# McPiFace-7Segment-V1.net
KiCad netlist of a schematic drawn in EAGLE
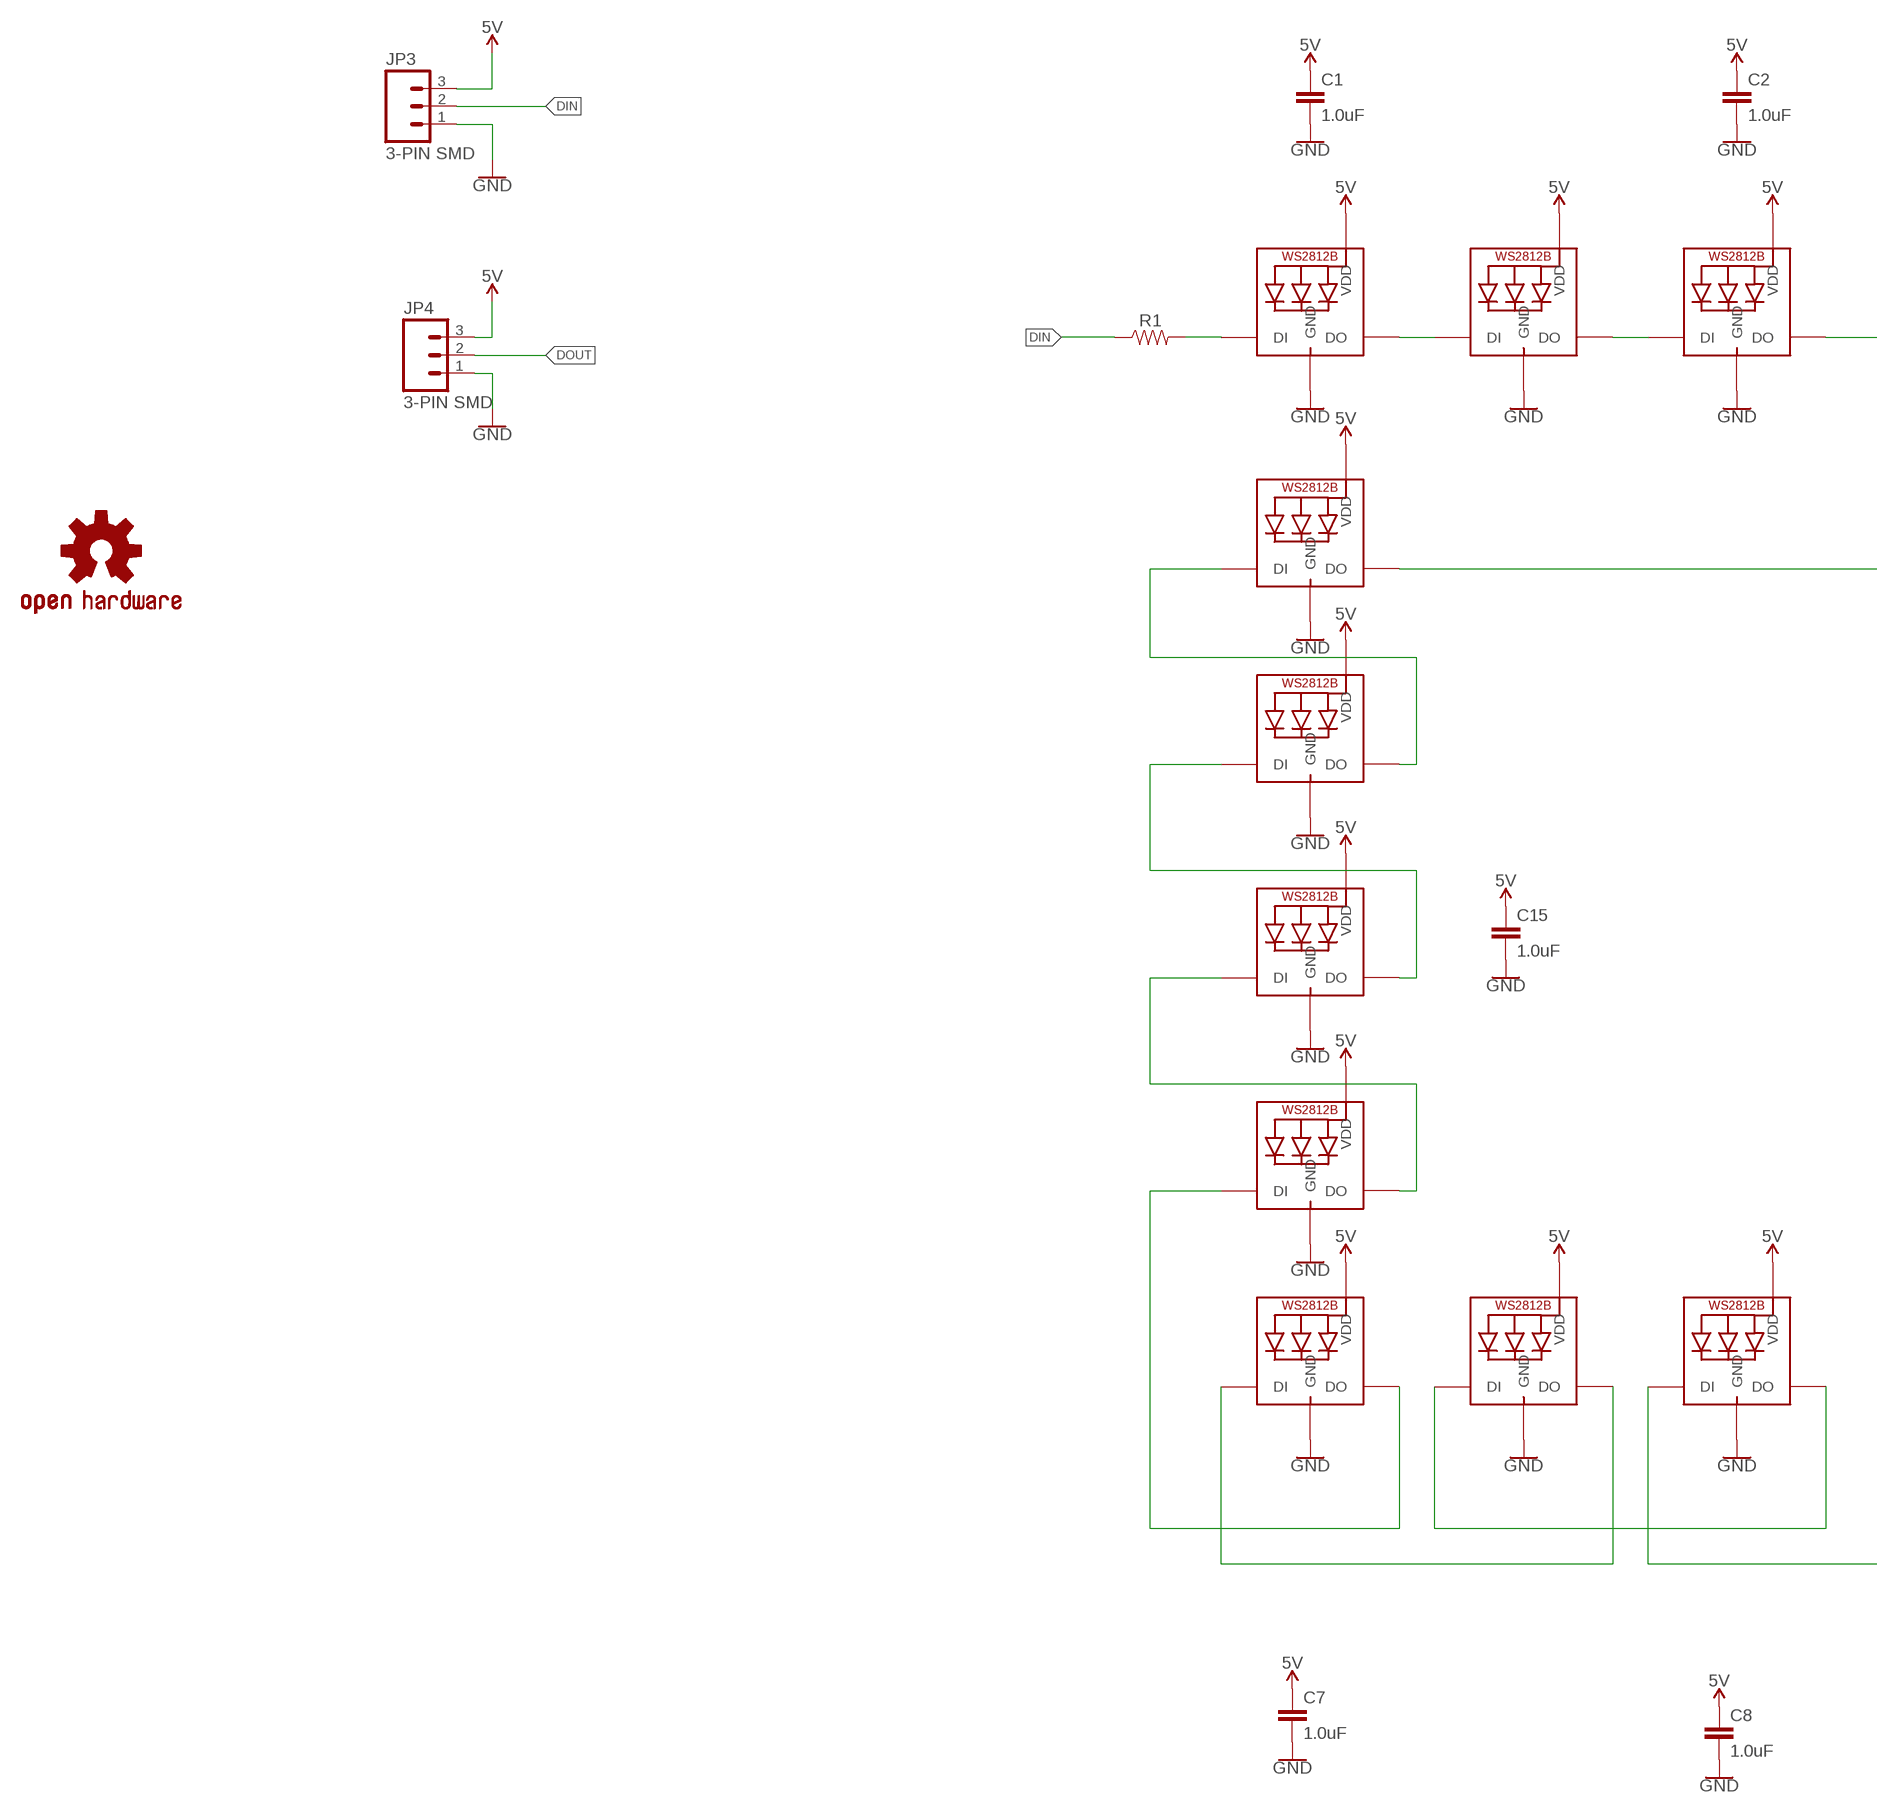
[diagram p0: schematic, sheet 1, part 1 of 2]
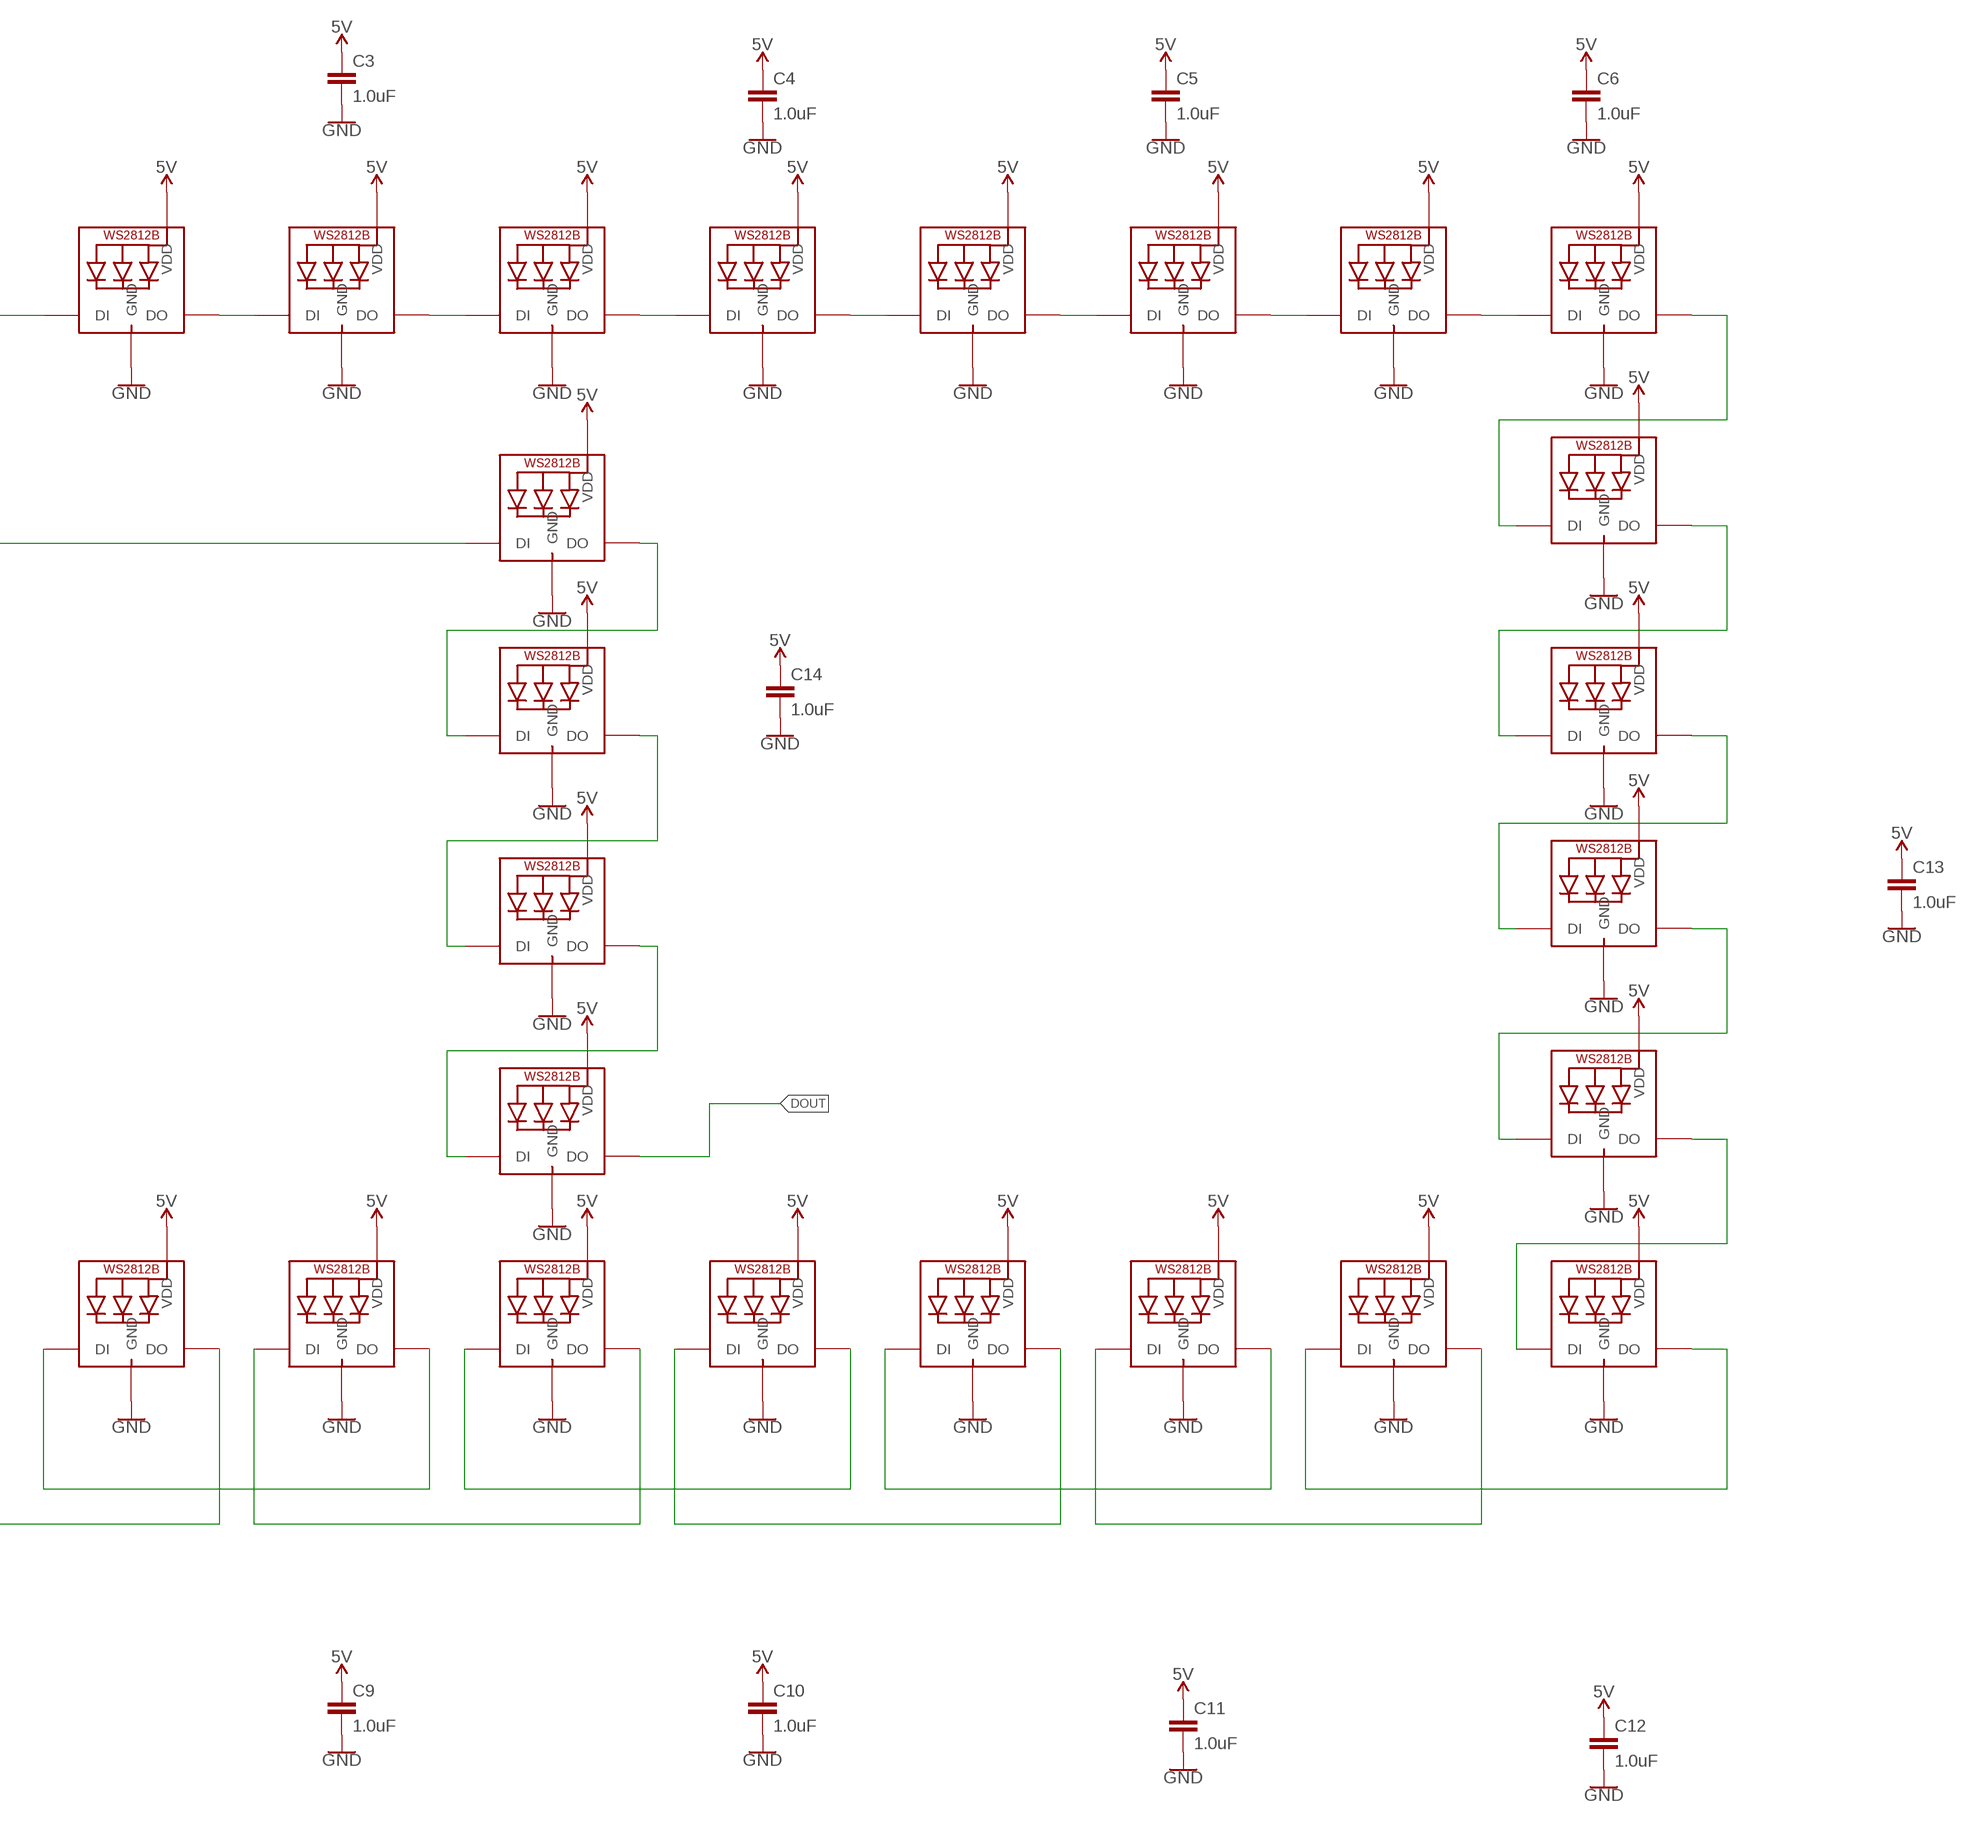
[diagram p1: schematic, sheet 1, part 2 of 2]

(export (version "E")
  (design (tool "Eeschema 10.0.6"))
  (components
    (comp (ref "C1")
      (value "1.0uF")
      (footprint "eagle-import:0805-CAP")
      (libsource (lib "eagle-import") (part "1.0UF-25V-+80/-20(0805){dblquote}"))
    )
    (comp (ref "C2")
      (value "1.0uF")
      (footprint "eagle-import:0805-CAP")
      (libsource (lib "eagle-import") (part "1.0UF-25V-+80/-20(0805){dblquote}"))
    )
    (comp (ref "C3")
      (value "1.0uF")
      (footprint "eagle-import:0805-CAP")
      (libsource (lib "eagle-import") (part "1.0UF-25V-+80/-20(0805){dblquote}"))
    )
    (comp (ref "C4")
      (value "1.0uF")
      (footprint "eagle-import:0805-CAP")
      (libsource (lib "eagle-import") (part "1.0UF-25V-+80/-20(0805){dblquote}"))
    )
    (comp (ref "C5")
      (value "1.0uF")
      (footprint "eagle-import:0805-CAP")
      (libsource (lib "eagle-import") (part "1.0UF-25V-+80/-20(0805){dblquote}"))
    )
    (comp (ref "C6")
      (value "1.0uF")
      (footprint "eagle-import:0805-CAP")
      (libsource (lib "eagle-import") (part "1.0UF-25V-+80/-20(0805){dblquote}"))
    )
    (comp (ref "C7")
      (value "1.0uF")
      (footprint "eagle-import:0805-CAP")
      (libsource (lib "eagle-import") (part "1.0UF-25V-+80/-20(0805){dblquote}"))
    )
    (comp (ref "C8")
      (value "1.0uF")
      (footprint "eagle-import:0805-CAP")
      (libsource (lib "eagle-import") (part "1.0UF-25V-+80/-20(0805){dblquote}"))
    )
    (comp (ref "C9")
      (value "1.0uF")
      (footprint "eagle-import:0805-CAP")
      (libsource (lib "eagle-import") (part "1.0UF-25V-+80/-20(0805){dblquote}"))
    )
    (comp (ref "C10")
      (value "1.0uF")
      (footprint "eagle-import:0805-CAP")
      (libsource (lib "eagle-import") (part "1.0UF-25V-+80/-20(0805){dblquote}"))
    )
    (comp (ref "C11")
      (value "1.0uF")
      (footprint "eagle-import:0805-CAP")
      (libsource (lib "eagle-import") (part "1.0UF-25V-+80/-20(0805){dblquote}"))
    )
    (comp (ref "C12")
      (value "1.0uF")
      (footprint "eagle-import:0805-CAP")
      (libsource (lib "eagle-import") (part "1.0UF-25V-+80/-20(0805){dblquote}"))
    )
    (comp (ref "C13")
      (value "1.0uF")
      (footprint "eagle-import:0805-CAP")
      (libsource (lib "eagle-import") (part "1.0UF-25V-+80/-20(0805){dblquote}"))
    )
    (comp (ref "C14")
      (value "1.0uF")
      (footprint "eagle-import:0805-CAP")
      (libsource (lib "eagle-import") (part "1.0UF-25V-+80/-20(0805){dblquote}"))
    )
    (comp (ref "C15")
      (value "1.0uF")
      (footprint "eagle-import:0805-CAP")
      (libsource (lib "eagle-import") (part "1.0UF-25V-+80/-20(0805){dblquote}"))
    )
    (comp (ref "JP3")
      (value "3-PIN SMD")
      (footprint "eagle-import:JST-3-SMD")
      (libsource (lib "eagle-import") (part "M03JST-SMD"))
    )
    (comp (ref "JP4")
      (value "3-PIN SMD")
      (footprint "eagle-import:JST-3-SMD")
      (libsource (lib "eagle-import") (part "M03JST-SMD"))
    )
    (comp (ref "LED1")
      (value "WS2812B5050")
      (footprint "eagle-import:WS2812B")
      (libsource (lib "eagle-import") (part "WS2812B5050"))
    )
    (comp (ref "LED2")
      (value "WS2812B5050")
      (footprint "eagle-import:WS2812B")
      (libsource (lib "eagle-import") (part "WS2812B5050"))
    )
    (comp (ref "LED3")
      (value "WS2812B5050")
      (footprint "eagle-import:WS2812B")
      (libsource (lib "eagle-import") (part "WS2812B5050"))
    )
    (comp (ref "LED4")
      (value "WS2812B5050")
      (footprint "eagle-import:WS2812B")
      (libsource (lib "eagle-import") (part "WS2812B5050"))
    )
    (comp (ref "LED5")
      (value "WS2812B5050")
      (footprint "eagle-import:WS2812B")
      (libsource (lib "eagle-import") (part "WS2812B5050"))
    )
    (comp (ref "LED6")
      (value "WS2812B5050")
      (footprint "eagle-import:WS2812B")
      (libsource (lib "eagle-import") (part "WS2812B5050"))
    )
    (comp (ref "LED7")
      (value "WS2812B5050")
      (footprint "eagle-import:WS2812B")
      (libsource (lib "eagle-import") (part "WS2812B5050"))
    )
    (comp (ref "LED8")
      (value "WS2812B5050")
      (footprint "eagle-import:WS2812B")
      (libsource (lib "eagle-import") (part "WS2812B5050"))
    )
    (comp (ref "LED9")
      (value "WS2812B5050")
      (footprint "eagle-import:WS2812B")
      (libsource (lib "eagle-import") (part "WS2812B5050"))
    )
    (comp (ref "LED10")
      (value "WS2812B5050")
      (footprint "eagle-import:WS2812B")
      (libsource (lib "eagle-import") (part "WS2812B5050"))
    )
    (comp (ref "LED11")
      (value "WS2812B5050")
      (footprint "eagle-import:WS2812B")
      (libsource (lib "eagle-import") (part "WS2812B5050"))
    )
    (comp (ref "LED12")
      (value "WS2812B5050")
      (footprint "eagle-import:WS2812B")
      (libsource (lib "eagle-import") (part "WS2812B5050"))
    )
    (comp (ref "LED13")
      (value "WS2812B5050")
      (footprint "eagle-import:WS2812B")
      (libsource (lib "eagle-import") (part "WS2812B5050"))
    )
    (comp (ref "LED14")
      (value "WS2812B5050")
      (footprint "eagle-import:WS2812B")
      (libsource (lib "eagle-import") (part "WS2812B5050"))
    )
    (comp (ref "LED15")
      (value "WS2812B5050")
      (footprint "eagle-import:WS2812B")
      (libsource (lib "eagle-import") (part "WS2812B5050"))
    )
    (comp (ref "LED16")
      (value "WS2812B5050")
      (footprint "eagle-import:WS2812B")
      (libsource (lib "eagle-import") (part "WS2812B5050"))
    )
    (comp (ref "LED17")
      (value "WS2812B5050")
      (footprint "eagle-import:WS2812B")
      (libsource (lib "eagle-import") (part "WS2812B5050"))
    )
    (comp (ref "LED18")
      (value "WS2812B5050")
      (footprint "eagle-import:WS2812B")
      (libsource (lib "eagle-import") (part "WS2812B5050"))
    )
    (comp (ref "LED19")
      (value "WS2812B5050")
      (footprint "eagle-import:WS2812B")
      (libsource (lib "eagle-import") (part "WS2812B5050"))
    )
    (comp (ref "LED20")
      (value "WS2812B5050")
      (footprint "eagle-import:WS2812B")
      (libsource (lib "eagle-import") (part "WS2812B5050"))
    )
    (comp (ref "LED21")
      (value "WS2812B5050")
      (footprint "eagle-import:WS2812B")
      (libsource (lib "eagle-import") (part "WS2812B5050"))
    )
    (comp (ref "LED22")
      (value "WS2812B5050")
      (footprint "eagle-import:WS2812B")
      (libsource (lib "eagle-import") (part "WS2812B5050"))
    )
    (comp (ref "LED23")
      (value "WS2812B5050")
      (footprint "eagle-import:WS2812B")
      (libsource (lib "eagle-import") (part "WS2812B5050"))
    )
    (comp (ref "LED24")
      (value "WS2812B5050")
      (footprint "eagle-import:WS2812B")
      (libsource (lib "eagle-import") (part "WS2812B5050"))
    )
    (comp (ref "LED25")
      (value "WS2812B5050")
      (footprint "eagle-import:WS2812B")
      (libsource (lib "eagle-import") (part "WS2812B5050"))
    )
    (comp (ref "LED26")
      (value "WS2812B5050")
      (footprint "eagle-import:WS2812B")
      (libsource (lib "eagle-import") (part "WS2812B5050"))
    )
    (comp (ref "LED27")
      (value "WS2812B5050")
      (footprint "eagle-import:WS2812B")
      (libsource (lib "eagle-import") (part "WS2812B5050"))
    )
    (comp (ref "LED28")
      (value "WS2812B5050")
      (footprint "eagle-import:WS2812B")
      (libsource (lib "eagle-import") (part "WS2812B5050"))
    )
    (comp (ref "LED29")
      (value "WS2812B5050")
      (footprint "eagle-import:WS2812B")
      (libsource (lib "eagle-import") (part "WS2812B5050"))
    )
    (comp (ref "LED30")
      (value "WS2812B5050")
      (footprint "eagle-import:WS2812B")
      (libsource (lib "eagle-import") (part "WS2812B5050"))
    )
    (comp (ref "LED31")
      (value "WS2812B5050")
      (footprint "eagle-import:WS2812B")
      (libsource (lib "eagle-import") (part "WS2812B5050"))
    )
    (comp (ref "LED32")
      (value "WS2812B5050")
      (footprint "eagle-import:WS2812B")
      (libsource (lib "eagle-import") (part "WS2812B5050"))
    )
    (comp (ref "LED33")
      (value "WS2812B5050")
      (footprint "eagle-import:WS2812B")
      (libsource (lib "eagle-import") (part "WS2812B5050"))
    )
    (comp (ref "LED34")
      (value "WS2812B5050")
      (footprint "eagle-import:WS2812B")
      (libsource (lib "eagle-import") (part "WS2812B5050"))
    )
    (comp (ref "LOGO1")
      (value "OSHW-LOGOL")
      (footprint "eagle-import:OSHW-LOGO-L")
      (libsource (lib "eagle-import") (part "OSHW-LOGOL"))
    )
    (comp (ref "R1")
      (value "RESISTOR0805")
      (footprint "eagle-import:0805")
      (libsource (lib "eagle-import") (part "RESISTOR0805"))
    )
  )
  (nets
    (net (code "1") (name "5V") (class "Default")
      (node (ref "C1") (pin "1") (pinfunction "1_1") (pintype "passive"))
      (node (ref "C10") (pin "1") (pinfunction "1_1") (pintype "passive"))
      (node (ref "C11") (pin "1") (pinfunction "1_1") (pintype "passive"))
      (node (ref "C12") (pin "1") (pinfunction "1_1") (pintype "passive"))
      (node (ref "C13") (pin "1") (pinfunction "1_1") (pintype "passive"))
      (node (ref "C14") (pin "1") (pinfunction "1_1") (pintype "passive"))
      (node (ref "C15") (pin "1") (pinfunction "1_1") (pintype "passive"))
      (node (ref "C2") (pin "1") (pinfunction "1_1") (pintype "passive"))
      (node (ref "C3") (pin "1") (pinfunction "1_1") (pintype "passive"))
      (node (ref "C4") (pin "1") (pinfunction "1_1") (pintype "passive"))
      (node (ref "C5") (pin "1") (pinfunction "1_1") (pintype "passive"))
      (node (ref "C6") (pin "1") (pinfunction "1_1") (pintype "passive"))
      (node (ref "C7") (pin "1") (pinfunction "1_1") (pintype "passive"))
      (node (ref "C8") (pin "1") (pinfunction "1_1") (pintype "passive"))
      (node (ref "C9") (pin "1") (pinfunction "1_1") (pintype "passive"))
      (node (ref "JP3") (pin "3") (pinfunction "3_3") (pintype "passive"))
      (node (ref "JP4") (pin "3") (pinfunction "3_3") (pintype "passive"))
      (node (ref "LED1") (pin "1-VDD") (pinfunction "VDD_1-VDD") (pintype "power_in"))
      (node (ref "LED10") (pin "1-VDD") (pinfunction "VDD_1-VDD") (pintype "power_in"))
      (node (ref "LED11") (pin "1-VDD") (pinfunction "VDD_1-VDD") (pintype "power_in"))
      (node (ref "LED12") (pin "1-VDD") (pinfunction "VDD_1-VDD") (pintype "power_in"))
      (node (ref "LED13") (pin "1-VDD") (pinfunction "VDD_1-VDD") (pintype "power_in"))
      (node (ref "LED14") (pin "1-VDD") (pinfunction "VDD_1-VDD") (pintype "power_in"))
      (node (ref "LED15") (pin "1-VDD") (pinfunction "VDD_1-VDD") (pintype "power_in"))
      (node (ref "LED16") (pin "1-VDD") (pinfunction "VDD_1-VDD") (pintype "power_in"))
      (node (ref "LED17") (pin "1-VDD") (pinfunction "VDD_1-VDD") (pintype "power_in"))
      (node (ref "LED18") (pin "1-VDD") (pinfunction "VDD_1-VDD") (pintype "power_in"))
      (node (ref "LED19") (pin "1-VDD") (pinfunction "VDD_1-VDD") (pintype "power_in"))
      (node (ref "LED2") (pin "1-VDD") (pinfunction "VDD_1-VDD") (pintype "power_in"))
      (node (ref "LED20") (pin "1-VDD") (pinfunction "VDD_1-VDD") (pintype "power_in"))
      (node (ref "LED21") (pin "1-VDD") (pinfunction "VDD_1-VDD") (pintype "power_in"))
      (node (ref "LED22") (pin "1-VDD") (pinfunction "VDD_1-VDD") (pintype "power_in"))
      (node (ref "LED23") (pin "1-VDD") (pinfunction "VDD_1-VDD") (pintype "power_in"))
      (node (ref "LED24") (pin "1-VDD") (pinfunction "VDD_1-VDD") (pintype "power_in"))
      (node (ref "LED25") (pin "1-VDD") (pinfunction "VDD_1-VDD") (pintype "power_in"))
      (node (ref "LED26") (pin "1-VDD") (pinfunction "VDD_1-VDD") (pintype "power_in"))
      (node (ref "LED27") (pin "1-VDD") (pinfunction "VDD_1-VDD") (pintype "power_in"))
      (node (ref "LED28") (pin "1-VDD") (pinfunction "VDD_1-VDD") (pintype "power_in"))
      (node (ref "LED29") (pin "1-VDD") (pinfunction "VDD_1-VDD") (pintype "power_in"))
      (node (ref "LED3") (pin "1-VDD") (pinfunction "VDD_1-VDD") (pintype "power_in"))
      (node (ref "LED30") (pin "1-VDD") (pinfunction "VDD_1-VDD") (pintype "power_in"))
      (node (ref "LED31") (pin "1-VDD") (pinfunction "VDD_1-VDD") (pintype "power_in"))
      (node (ref "LED32") (pin "1-VDD") (pinfunction "VDD_1-VDD") (pintype "power_in"))
      (node (ref "LED33") (pin "1-VDD") (pinfunction "VDD_1-VDD") (pintype "power_in"))
      (node (ref "LED34") (pin "1-VDD") (pinfunction "VDD_1-VDD") (pintype "power_in"))
      (node (ref "LED4") (pin "1-VDD") (pinfunction "VDD_1-VDD") (pintype "power_in"))
      (node (ref "LED5") (pin "1-VDD") (pinfunction "VDD_1-VDD") (pintype "power_in"))
      (node (ref "LED6") (pin "1-VDD") (pinfunction "VDD_1-VDD") (pintype "power_in"))
      (node (ref "LED7") (pin "1-VDD") (pinfunction "VDD_1-VDD") (pintype "power_in"))
      (node (ref "LED8") (pin "1-VDD") (pinfunction "VDD_1-VDD") (pintype "power_in"))
      (node (ref "LED9") (pin "1-VDD") (pinfunction "VDD_1-VDD") (pintype "power_in"))
    )
    (net (code "2") (name "DIN") (class "Default")
      (node (ref "JP3") (pin "2") (pinfunction "2_2") (pintype "passive"))
      (node (ref "R1") (pin "1") (pinfunction "1_1") (pintype "passive"))
    )
    (net (code "3") (name "DOUT") (class "Default")
      (node (ref "JP4") (pin "2") (pinfunction "2_2") (pintype "passive"))
      (node (ref "LED15") (pin "2-DOUT") (pinfunction "DO_2-DOUT") (pintype "output"))
    )
    (net (code "4") (name "GND") (class "Default")
      (node (ref "C1") (pin "2") (pinfunction "2_2") (pintype "passive"))
      (node (ref "C10") (pin "2") (pinfunction "2_2") (pintype "passive"))
      (node (ref "C11") (pin "2") (pinfunction "2_2") (pintype "passive"))
      (node (ref "C12") (pin "2") (pinfunction "2_2") (pintype "passive"))
      (node (ref "C13") (pin "2") (pinfunction "2_2") (pintype "passive"))
      (node (ref "C14") (pin "2") (pinfunction "2_2") (pintype "passive"))
      (node (ref "C15") (pin "2") (pinfunction "2_2") (pintype "passive"))
      (node (ref "C2") (pin "2") (pinfunction "2_2") (pintype "passive"))
      (node (ref "C3") (pin "2") (pinfunction "2_2") (pintype "passive"))
      (node (ref "C4") (pin "2") (pinfunction "2_2") (pintype "passive"))
      (node (ref "C5") (pin "2") (pinfunction "2_2") (pintype "passive"))
      (node (ref "C6") (pin "2") (pinfunction "2_2") (pintype "passive"))
      (node (ref "C7") (pin "2") (pinfunction "2_2") (pintype "passive"))
      (node (ref "C8") (pin "2") (pinfunction "2_2") (pintype "passive"))
      (node (ref "C9") (pin "2") (pinfunction "2_2") (pintype "passive"))
      (node (ref "JP3") (pin "1") (pinfunction "1_1") (pintype "passive"))
      (node (ref "JP4") (pin "1") (pinfunction "1_1") (pintype "passive"))
      (node (ref "LED1") (pin "3-GND") (pinfunction "GND_3-GND") (pintype "power_in"))
      (node (ref "LED10") (pin "3-GND") (pinfunction "GND_3-GND") (pintype "power_in"))
      (node (ref "LED11") (pin "3-GND") (pinfunction "GND_3-GND") (pintype "power_in"))
      (node (ref "LED12") (pin "3-GND") (pinfunction "GND_3-GND") (pintype "power_in"))
      (node (ref "LED13") (pin "3-GND") (pinfunction "GND_3-GND") (pintype "power_in"))
      (node (ref "LED14") (pin "3-GND") (pinfunction "GND_3-GND") (pintype "power_in"))
      (node (ref "LED15") (pin "3-GND") (pinfunction "GND_3-GND") (pintype "power_in"))
      (node (ref "LED16") (pin "3-GND") (pinfunction "GND_3-GND") (pintype "power_in"))
      (node (ref "LED17") (pin "3-GND") (pinfunction "GND_3-GND") (pintype "power_in"))
      (node (ref "LED18") (pin "3-GND") (pinfunction "GND_3-GND") (pintype "power_in"))
      (node (ref "LED19") (pin "3-GND") (pinfunction "GND_3-GND") (pintype "power_in"))
      (node (ref "LED2") (pin "3-GND") (pinfunction "GND_3-GND") (pintype "power_in"))
      (node (ref "LED20") (pin "3-GND") (pinfunction "GND_3-GND") (pintype "power_in"))
      (node (ref "LED21") (pin "3-GND") (pinfunction "GND_3-GND") (pintype "power_in"))
      (node (ref "LED22") (pin "3-GND") (pinfunction "GND_3-GND") (pintype "power_in"))
      (node (ref "LED23") (pin "3-GND") (pinfunction "GND_3-GND") (pintype "power_in"))
      (node (ref "LED24") (pin "3-GND") (pinfunction "GND_3-GND") (pintype "power_in"))
      (node (ref "LED25") (pin "3-GND") (pinfunction "GND_3-GND") (pintype "power_in"))
      (node (ref "LED26") (pin "3-GND") (pinfunction "GND_3-GND") (pintype "power_in"))
      (node (ref "LED27") (pin "3-GND") (pinfunction "GND_3-GND") (pintype "power_in"))
      (node (ref "LED28") (pin "3-GND") (pinfunction "GND_3-GND") (pintype "power_in"))
      (node (ref "LED29") (pin "3-GND") (pinfunction "GND_3-GND") (pintype "power_in"))
      (node (ref "LED3") (pin "3-GND") (pinfunction "GND_3-GND") (pintype "power_in"))
      (node (ref "LED30") (pin "3-GND") (pinfunction "GND_3-GND") (pintype "power_in"))
      (node (ref "LED31") (pin "3-GND") (pinfunction "GND_3-GND") (pintype "power_in"))
      (node (ref "LED32") (pin "3-GND") (pinfunction "GND_3-GND") (pintype "power_in"))
      (node (ref "LED33") (pin "3-GND") (pinfunction "GND_3-GND") (pintype "power_in"))
      (node (ref "LED34") (pin "3-GND") (pinfunction "GND_3-GND") (pintype "power_in"))
      (node (ref "LED4") (pin "3-GND") (pinfunction "GND_3-GND") (pintype "power_in"))
      (node (ref "LED5") (pin "3-GND") (pinfunction "GND_3-GND") (pintype "power_in"))
      (node (ref "LED6") (pin "3-GND") (pinfunction "GND_3-GND") (pintype "power_in"))
      (node (ref "LED7") (pin "3-GND") (pinfunction "GND_3-GND") (pintype "power_in"))
      (node (ref "LED8") (pin "3-GND") (pinfunction "GND_3-GND") (pintype "power_in"))
      (node (ref "LED9") (pin "3-GND") (pinfunction "GND_3-GND") (pintype "power_in"))
    )
    (net (code "5") (name "Net-(LED1-DI)") (class "Default")
      (node (ref "LED1") (pin "4-DIN") (pinfunction "DI_4-DIN") (pintype "input"))
      (node (ref "R1") (pin "2") (pinfunction "2_2") (pintype "passive"))
    )
    (net (code "6") (name "Net-(LED1-DO)") (class "Default")
      (node (ref "LED1") (pin "2-DOUT") (pinfunction "DO_2-DOUT") (pintype "output"))
      (node (ref "LED2") (pin "4-DIN") (pinfunction "DI_4-DIN") (pintype "input"))
    )
    (net (code "7") (name "Net-(LED2-DO)") (class "Default")
      (node (ref "LED2") (pin "2-DOUT") (pinfunction "DO_2-DOUT") (pintype "output"))
      (node (ref "LED3") (pin "4-DIN") (pinfunction "DI_4-DIN") (pintype "input"))
    )
    (net (code "8") (name "Net-(LED3-DO)") (class "Default")
      (node (ref "LED3") (pin "2-DOUT") (pinfunction "DO_2-DOUT") (pintype "output"))
      (node (ref "LED4") (pin "4-DIN") (pinfunction "DI_4-DIN") (pintype "input"))
    )
    (net (code "9") (name "Net-(LED4-DO)") (class "Default")
      (node (ref "LED4") (pin "2-DOUT") (pinfunction "DO_2-DOUT") (pintype "output"))
      (node (ref "LED5") (pin "4-DIN") (pinfunction "DI_4-DIN") (pintype "input"))
    )
    (net (code "10") (name "Net-(LED5-DO)") (class "Default")
      (node (ref "LED5") (pin "2-DOUT") (pinfunction "DO_2-DOUT") (pintype "output"))
      (node (ref "LED6") (pin "4-DIN") (pinfunction "DI_4-DIN") (pintype "input"))
    )
    (net (code "11") (name "Net-(LED6-DO)") (class "Default")
      (node (ref "LED6") (pin "2-DOUT") (pinfunction "DO_2-DOUT") (pintype "output"))
      (node (ref "LED7") (pin "4-DIN") (pinfunction "DI_4-DIN") (pintype "input"))
    )
    (net (code "12") (name "Net-(LED7-DO)") (class "Default")
      (node (ref "LED7") (pin "2-DOUT") (pinfunction "DO_2-DOUT") (pintype "output"))
      (node (ref "LED8") (pin "4-DIN") (pinfunction "DI_4-DIN") (pintype "input"))
    )
    (net (code "13") (name "Net-(LED8-DO)") (class "Default")
      (node (ref "LED8") (pin "2-DOUT") (pinfunction "DO_2-DOUT") (pintype "output"))
      (node (ref "LED9") (pin "4-DIN") (pinfunction "DI_4-DIN") (pintype "input"))
    )
    (net (code "14") (name "Net-(LED10-DI)") (class "Default")
      (node (ref "LED10") (pin "4-DIN") (pinfunction "DI_4-DIN") (pintype "input"))
      (node (ref "LED9") (pin "2-DOUT") (pinfunction "DO_2-DOUT") (pintype "output"))
    )
    (net (code "15") (name "Net-(LED10-DO)") (class "Default")
      (node (ref "LED10") (pin "2-DOUT") (pinfunction "DO_2-DOUT") (pintype "output"))
      (node (ref "LED11") (pin "4-DIN") (pinfunction "DI_4-DIN") (pintype "input"))
    )
    (net (code "16") (name "Net-(LED11-DO)") (class "Default")
      (node (ref "LED11") (pin "2-DOUT") (pinfunction "DO_2-DOUT") (pintype "output"))
      (node (ref "LED17") (pin "4-DIN") (pinfunction "DI_4-DIN") (pintype "input"))
    )
    (net (code "17") (name "Net-(LED12-DI)") (class "Default")
      (node (ref "LED12") (pin "4-DIN") (pinfunction "DI_4-DIN") (pintype "input"))
      (node (ref "LED34") (pin "2-DOUT") (pinfunction "DO_2-DOUT") (pintype "output"))
    )
    (net (code "18") (name "Net-(LED12-DO)") (class "Default")
      (node (ref "LED12") (pin "2-DOUT") (pinfunction "DO_2-DOUT") (pintype "output"))
      (node (ref "LED13") (pin "4-DIN") (pinfunction "DI_4-DIN") (pintype "input"))
    )
    (net (code "19") (name "Net-(LED13-DO)") (class "Default")
      (node (ref "LED13") (pin "2-DOUT") (pinfunction "DO_2-DOUT") (pintype "output"))
      (node (ref "LED14") (pin "4-DIN") (pinfunction "DI_4-DIN") (pintype "input"))
    )
    (net (code "20") (name "Net-(LED14-DO)") (class "Default")
      (node (ref "LED14") (pin "2-DOUT") (pinfunction "DO_2-DOUT") (pintype "output"))
      (node (ref "LED15") (pin "4-DIN") (pinfunction "DI_4-DIN") (pintype "input"))
    )
    (net (code "21") (name "Net-(LED16-DI)") (class "Default")
      (node (ref "LED16") (pin "4-DIN") (pinfunction "DI_4-DIN") (pintype "input"))
      (node (ref "LED25") (pin "2-DOUT") (pinfunction "DO_2-DOUT") (pintype "output"))
    )
    (net (code "22") (name "Net-(LED16-DO)") (class "Default")
      (node (ref "LED16") (pin "2-DOUT") (pinfunction "DO_2-DOUT") (pintype "output"))
      (node (ref "LED26") (pin "4-DIN") (pinfunction "DI_4-DIN") (pintype "input"))
    )
    (net (code "23") (name "Net-(LED17-DO)") (class "Default")
      (node (ref "LED17") (pin "2-DOUT") (pinfunction "DO_2-DOUT") (pintype "output"))
      (node (ref "LED18") (pin "4-DIN") (pinfunction "DI_4-DIN") (pintype "input"))
    )
    (net (code "24") (name "Net-(LED18-DO)") (class "Default")
      (node (ref "LED18") (pin "2-DOUT") (pinfunction "DO_2-DOUT") (pintype "output"))
      (node (ref "LED19") (pin "4-DIN") (pinfunction "DI_4-DIN") (pintype "input"))
    )
    (net (code "25") (name "Net-(LED19-DO)") (class "Default")
      (node (ref "LED19") (pin "2-DOUT") (pinfunction "DO_2-DOUT") (pintype "output"))
      (node (ref "LED20") (pin "4-DIN") (pinfunction "DI_4-DIN") (pintype "input"))
    )
    (net (code "26") (name "Net-(LED20-DO)") (class "Default")
      (node (ref "LED20") (pin "2-DOUT") (pinfunction "DO_2-DOUT") (pintype "output"))
      (node (ref "LED21") (pin "4-DIN") (pinfunction "DI_4-DIN") (pintype "input"))
    )
    (net (code "27") (name "Net-(LED21-DO)") (class "Default")
      (node (ref "LED21") (pin "2-DOUT") (pinfunction "DO_2-DOUT") (pintype "output"))
      (node (ref "LED22") (pin "4-DIN") (pinfunction "DI_4-DIN") (pintype "input"))
    )
    (net (code "28") (name "Net-(LED22-DO)") (class "Default")
      (node (ref "LED22") (pin "2-DOUT") (pinfunction "DO_2-DOUT") (pintype "output"))
      (node (ref "LED23") (pin "4-DIN") (pinfunction "DI_4-DIN") (pintype "input"))
    )
    (net (code "29") (name "Net-(LED23-DO)") (class "Default")
      (node (ref "LED23") (pin "2-DOUT") (pinfunction "DO_2-DOUT") (pintype "output"))
      (node (ref "LED24") (pin "4-DIN") (pinfunction "DI_4-DIN") (pintype "input"))
    )
    (net (code "30") (name "Net-(LED24-DO)") (class "Default")
      (node (ref "LED24") (pin "2-DOUT") (pinfunction "DO_2-DOUT") (pintype "output"))
      (node (ref "LED25") (pin "4-DIN") (pinfunction "DI_4-DIN") (pintype "input"))
    )
    (net (code "31") (name "Net-(LED26-DO)") (class "Default")
      (node (ref "LED26") (pin "2-DOUT") (pinfunction "DO_2-DOUT") (pintype "output"))
      (node (ref "LED27") (pin "4-DIN") (pinfunction "DI_4-DIN") (pintype "input"))
    )
    (net (code "32") (name "Net-(LED27-DO)") (class "Default")
      (node (ref "LED27") (pin "2-DOUT") (pinfunction "DO_2-DOUT") (pintype "output"))
      (node (ref "LED28") (pin "4-DIN") (pinfunction "DI_4-DIN") (pintype "input"))
    )
    (net (code "33") (name "Net-(LED28-DO)") (class "Default")
      (node (ref "LED28") (pin "2-DOUT") (pinfunction "DO_2-DOUT") (pintype "output"))
      (node (ref "LED29") (pin "4-DIN") (pinfunction "DI_4-DIN") (pintype "input"))
    )
    (net (code "34") (name "Net-(LED29-DO)") (class "Default")
      (node (ref "LED29") (pin "2-DOUT") (pinfunction "DO_2-DOUT") (pintype "output"))
      (node (ref "LED30") (pin "4-DIN") (pinfunction "DI_4-DIN") (pintype "input"))
    )
    (net (code "35") (name "Net-(LED30-DO)") (class "Default")
      (node (ref "LED30") (pin "2-DOUT") (pinfunction "DO_2-DOUT") (pintype "output"))
      (node (ref "LED31") (pin "4-DIN") (pinfunction "DI_4-DIN") (pintype "input"))
    )
    (net (code "36") (name "Net-(LED31-DO)") (class "Default")
      (node (ref "LED31") (pin "2-DOUT") (pinfunction "DO_2-DOUT") (pintype "output"))
      (node (ref "LED32") (pin "4-DIN") (pinfunction "DI_4-DIN") (pintype "input"))
    )
    (net (code "37") (name "Net-(LED32-DO)") (class "Default")
      (node (ref "LED32") (pin "2-DOUT") (pinfunction "DO_2-DOUT") (pintype "output"))
      (node (ref "LED33") (pin "4-DIN") (pinfunction "DI_4-DIN") (pintype "input"))
    )
    (net (code "38") (name "Net-(LED33-DO)") (class "Default")
      (node (ref "LED33") (pin "2-DOUT") (pinfunction "DO_2-DOUT") (pintype "output"))
      (node (ref "LED34") (pin "4-DIN") (pinfunction "DI_4-DIN") (pintype "input"))
    )
  )
)
